# S2_WirelessAudio_CC8530.net
KiCad netlist of a schematic drawn in Altium Designer
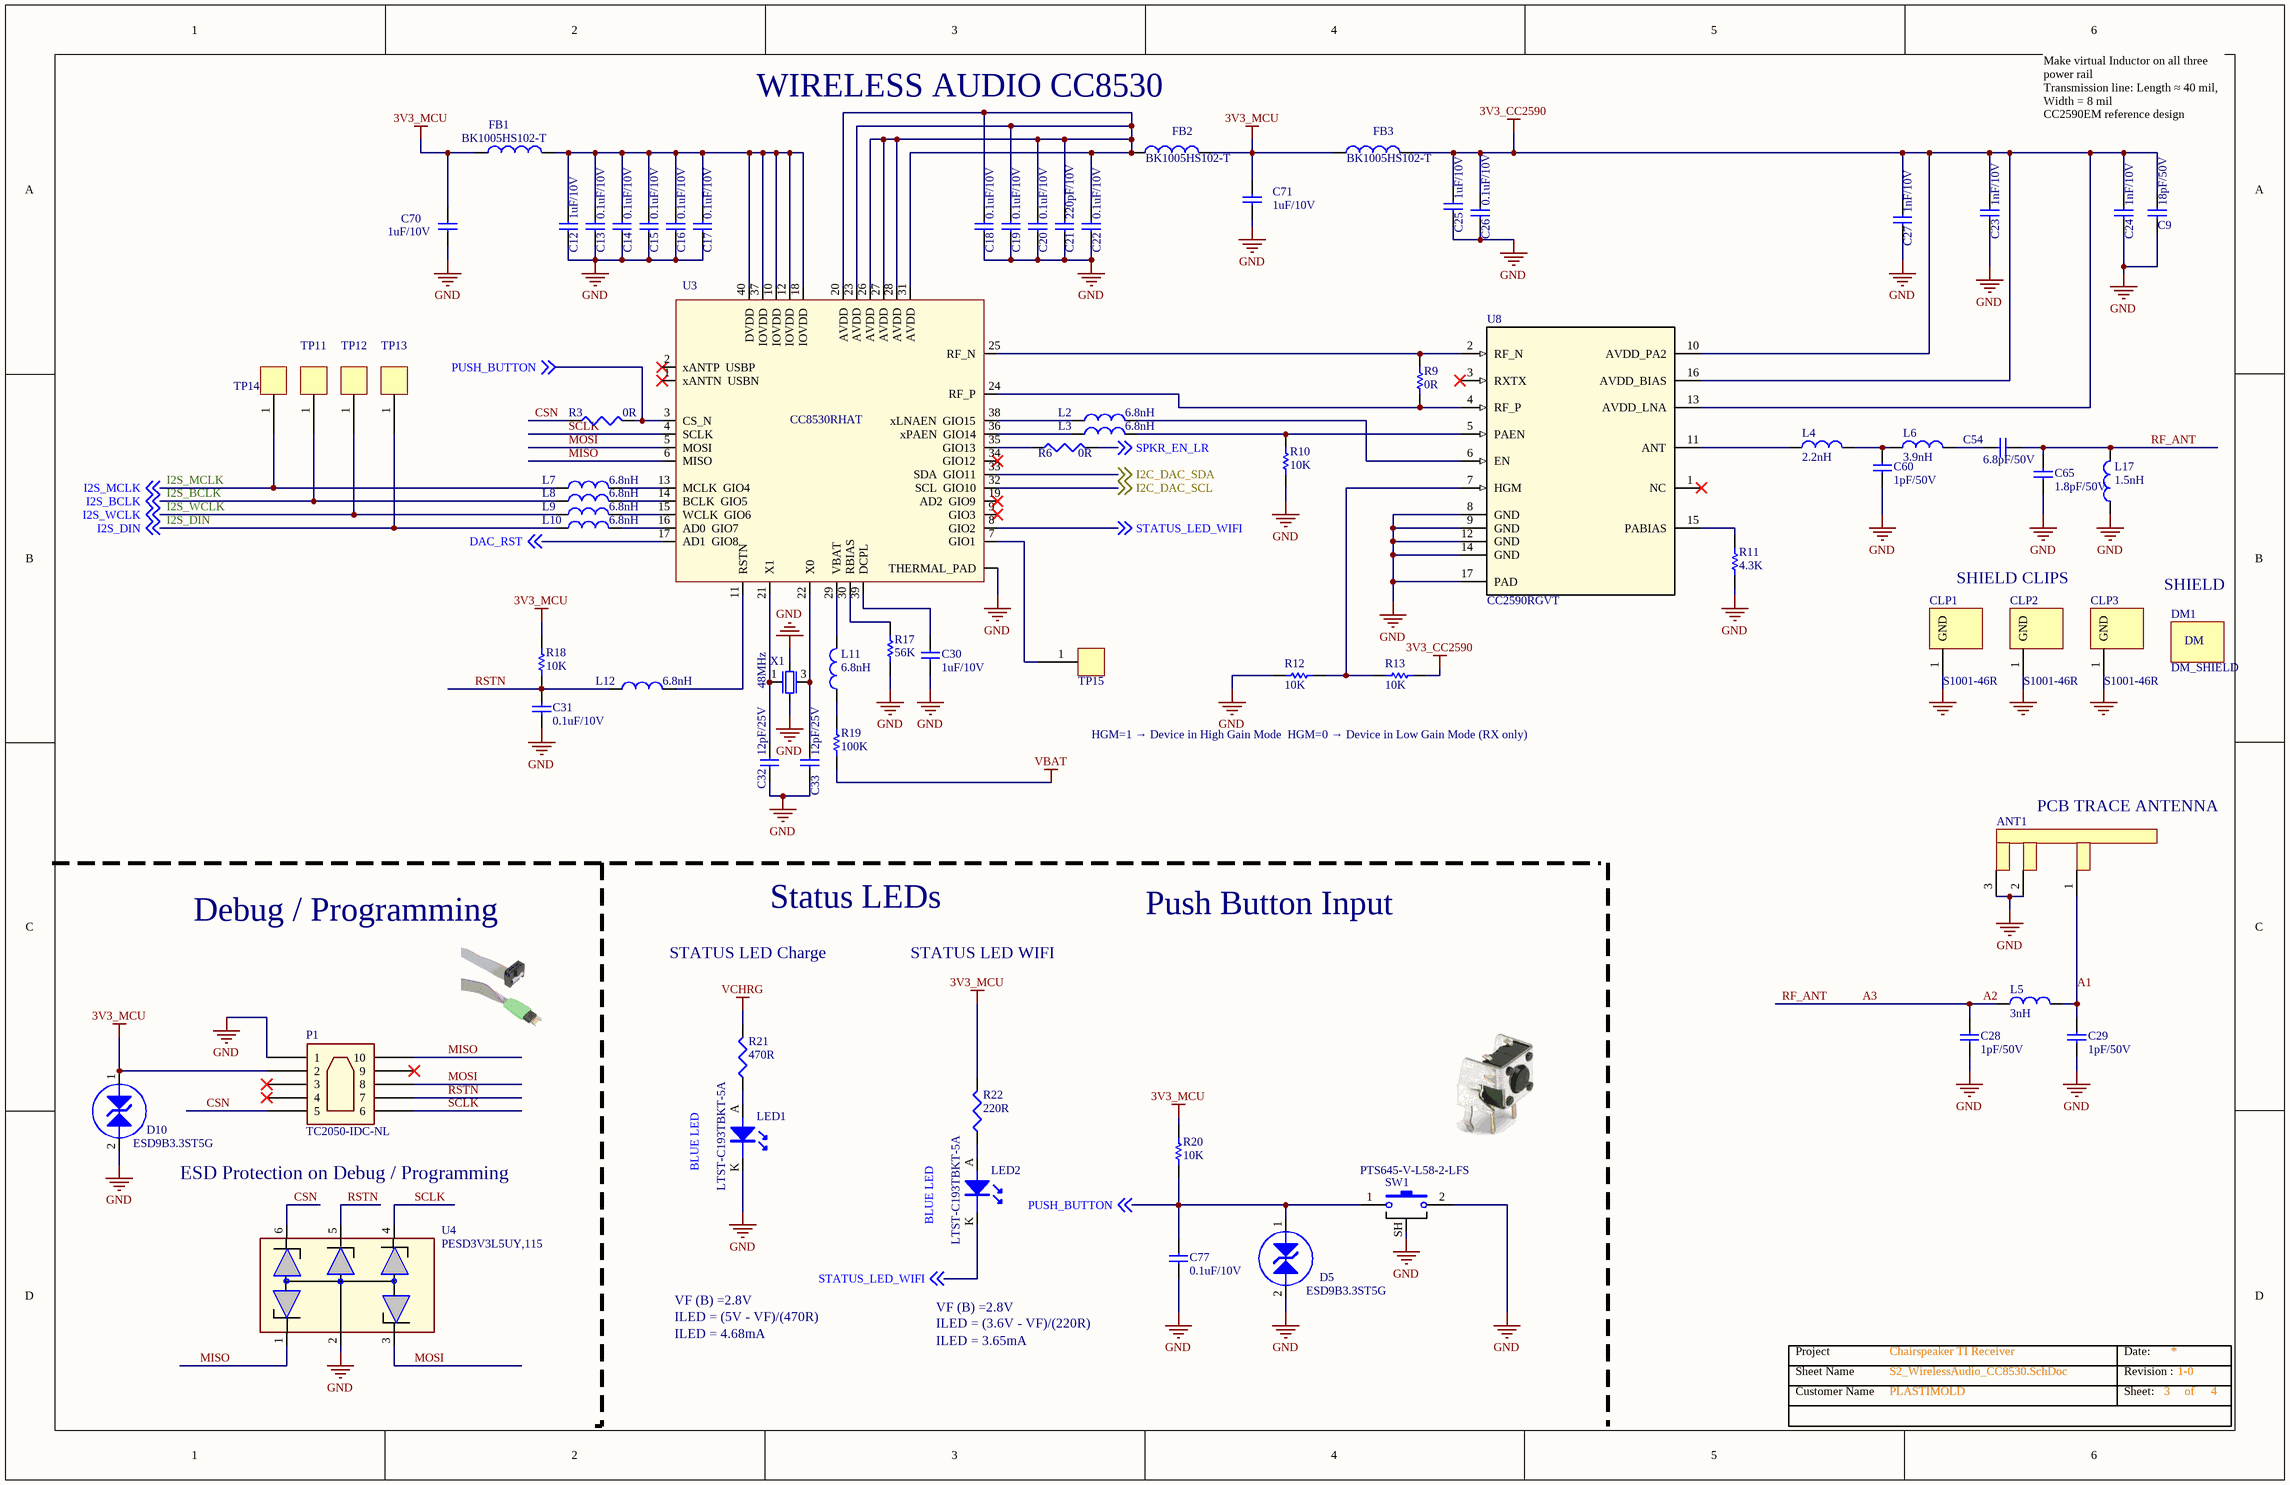
[diagram p0: S2_WirelessAudio_CC8530.SchDoc]

(export (version "E")
  (design (tool "Eeschema 10.0.6"))
  (components
    (comp (ref "ANT1")
      (value "INVERTED F ANTENNA")
      (footprint "ANT")
      (description "=Description1")
      (libsource (lib "TV-Pillow_REV0-1") (part "INVERTED_F"))
    )
    (comp (ref "C9")
      (value "18pF/50V")
      (footprint "CAP_0402_(M1005)")
      (description "=Description1")
      (libsource (lib "Symbol") (part "CAP"))
    )
    (comp (ref "C12")
      (value "1uF/10V")
      (footprint "CAP_0402_(M1005)")
      (description "=Description1")
      (libsource (lib "Nordic Passive DB") (part "CAP"))
    )
    (comp (ref "C13")
      (value "0.1uF/10V")
      (footprint "CAP_0402_(M1005)")
      (description "=Description1")
      (libsource (lib "RC50_REV0-1_INT") (part "CAP_1"))
    )
    (comp (ref "C14")
      (value "0.1uF/10V")
      (footprint "CAP_0402_(M1005)")
      (description "=Description1")
      (libsource (lib "RC50_REV0-1_INT") (part "CAP_1"))
    )
    (comp (ref "C15")
      (value "0.1uF/10V")
      (footprint "CAP_0402_(M1005)")
      (description "=Description1")
      (libsource (lib "RC50_REV0-1_INT") (part "CAP_1"))
    )
    (comp (ref "C16")
      (value "0.1uF/10V")
      (footprint "CAP_0402_(M1005)")
      (description "=Description1")
      (libsource (lib "RC50_REV0-1_INT") (part "CAP_1"))
    )
    (comp (ref "C17")
      (value "0.1uF/10V")
      (footprint "CAP_0402_(M1005)")
      (description "=Description1")
      (libsource (lib "RC50_REV0-1_INT") (part "CAP_1"))
    )
    (comp (ref "C18")
      (value "0.1uF/10V")
      (footprint "CAP_0402_(M1005)")
      (description "=Description1")
      (libsource (lib "RC50_REV0-1_INT") (part "CAP_1"))
    )
    (comp (ref "C19")
      (value "0.1uF/10V")
      (footprint "CAP_0402_(M1005)")
      (description "=Description1")
      (libsource (lib "RC50_REV0-1_INT") (part "CAP_1"))
    )
    (comp (ref "C20")
      (value "0.1uF/10V")
      (footprint "CAP_0402_(M1005)")
      (description "=Description1")
      (libsource (lib "RC50_REV0-1_INT") (part "CAP_1"))
    )
    (comp (ref "C21")
      (value "220pF/10V")
      (footprint "CAP_0402_(M1005)")
      (description "=Description1")
      (libsource (lib "RC50_REV0-1_INT") (part "CAP_1"))
    )
    (comp (ref "C22")
      (value "0.1uF/10V")
      (footprint "CAP_0402_(M1005)")
      (description "=Description1")
      (libsource (lib "RC50_REV0-1_INT") (part "CAP_1"))
    )
    (comp (ref "C23")
      (value "1nF/10V")
      (footprint "CAP_0402_(M1005)")
      (description "=Description1")
      (libsource (lib "RC50_REV0-1_INT") (part "CAP_1"))
    )
    (comp (ref "C24")
      (value "1nF/10V")
      (footprint "CAP_0402_(M1005)")
      (description "=Description1")
      (libsource (lib "RC50_REV0-1_INT") (part "CAP_1"))
    )
    (comp (ref "C25")
      (value "1uF/10V")
      (footprint "CAP_0402_(M1005)")
      (description "=Description1")
      (libsource (lib "Nordic Passive DB") (part "CAP"))
    )
    (comp (ref "C26")
      (value "0.1uF/10V")
      (footprint "CAP_0402_(M1005)")
      (description "=Description1")
      (libsource (lib "RC50_REV0-1_INT") (part "CAP_1"))
    )
    (comp (ref "C27")
      (value "1nF/10V")
      (footprint "CAP_0402_(M1005)")
      (description "=Description1")
      (libsource (lib "RC50_REV0-1_INT") (part "CAP_1"))
    )
    (comp (ref "C28")
      (value "1pF/50V")
      (footprint "CAP_0402_(M1005)")
      (description "=Description1")
      (libsource (lib "Symbol") (part "CAP"))
    )
    (comp (ref "C29")
      (value "1pF/50V")
      (footprint "CAP_0402_(M1005)")
      (description "=Description1")
      (libsource (lib "Symbol") (part "CAP"))
    )
    (comp (ref "C30")
      (value "1uF/10V")
      (footprint "CAP_0402_(M1005)")
      (description "=Description1")
      (libsource (lib "Nordic Passive DB") (part "CAP"))
    )
    (comp (ref "C31")
      (value "0.1uF/10V")
      (footprint "CAP_0402_(M1005)")
      (description "=Description1")
      (libsource (lib "RC50_REV0-1_INT") (part "CAP_1"))
    )
    (comp (ref "C32")
      (value "12pF/25V")
      (footprint "CAP_0402_(M1005)")
      (description "=Description1")
      (libsource (lib "RC50_REV0-1_INT") (part "CAP_1"))
    )
    (comp (ref "C33")
      (value "12pF/25V")
      (footprint "CAP_0402_(M1005)")
      (description "=Description1")
      (libsource (lib "RC50_REV0-1_INT") (part "CAP_1"))
    )
    (comp (ref "C54")
      (value "6.8pF/50V")
      (footprint "CAP_0402_(M1005)")
      (description "=Description1")
      (libsource (lib "Symbol") (part "CAP"))
    )
    (comp (ref "C60")
      (value "1pF/50V")
      (footprint "CAP_0402_(M1005)")
      (description "=Description1")
      (libsource (lib "Symbol") (part "CAP"))
    )
    (comp (ref "C65")
      (value "1.8pF/50V")
      (footprint "CAP_0402_(M1005)")
      (description "=Description1")
      (libsource (lib "Symbol") (part "CAP"))
    )
    (comp (ref "C70")
      (value "1uF/10V")
      (footprint "CAP_0402_(M1005)")
      (description "=Description1")
      (libsource (lib "Nordic Passive DB") (part "CAP"))
    )
    (comp (ref "C71")
      (value "1uF/10V")
      (footprint "CAP_0402_(M1005)")
      (description "=Description1")
      (libsource (lib "Nordic Passive DB") (part "CAP"))
    )
    (comp (ref "C77")
      (value "0.1uF/10V")
      (footprint "CAP_0402_(M1005)")
      (description "=Description1")
      (libsource (lib "RC50_REV0-1_INT") (part "CAP_1"))
    )
    (comp (ref "CLP1")
      (value "S1001-46R")
      (footprint "S1001-46R")
      (description "=Description1")
      (libsource (lib "TV-Pillow_REV0-1") (part "S2711-46R"))
    )
    (comp (ref "CLP2")
      (value "S1001-46R")
      (footprint "S1001-46R")
      (description "=Description1")
      (libsource (lib "TV-Pillow_REV0-1") (part "S2711-46R"))
    )
    (comp (ref "CLP3")
      (value "S1001-46R")
      (footprint "S1001-46R")
      (description "=Description1")
      (libsource (lib "TV-Pillow_REV0-1") (part "S2711-46R"))
    )
    (comp (ref "D5")
      (value "ESD9B3.3ST5G")
      (footprint "SOD-923-BI-DIRECTIONAL")
      (description "TVS DIODE 5V 15.5V 0402")
      (libsource (lib "APC_SCH.") (part "TVS-DIODE"))
    )
    (comp (ref "D10")
      (value "ESD9B3.3ST5G")
      (footprint "SOD-923-BI-DIRECTIONAL")
      (description "TVS DIODE 5V 15.5V 0402")
      (libsource (lib "APC_SCH.") (part "TVS-DIODE"))
    )
    (comp (ref "DM1")
      (value "DM_SHIELD")
      (description "=Description1")
      (libsource (lib "TV-Pillow_REV0-1") (part "DM_SHIELD"))
    )
    (comp (ref "FB1")
      (value "BK1005HS102-T")
      (footprint "IND_0402_(M1005)")
      (description "=Description1")
      (libsource (lib "APC_SCH") (part "FERRITE BEAD"))
    )
    (comp (ref "FB2")
      (value "BK1005HS102-T")
      (footprint "IND_0402_(M1005)")
      (description "=Description1")
      (libsource (lib "APC_SCH") (part "FERRITE BEAD"))
    )
    (comp (ref "FB3")
      (value "BK1005HS102-T")
      (footprint "IND_0402_(M1005)")
      (description "=Description1")
      (libsource (lib "APC_SCH") (part "FERRITE BEAD"))
    )
    (comp (ref "L2")
      (value "6.8nH")
      (footprint "IND_0402_(M1005)")
      (description "=Description1")
      (libsource (lib "Symbol") (part "IND"))
    )
    (comp (ref "L3")
      (value "6.8nH")
      (footprint "IND_0402_(M1005)")
      (description "=Description1")
      (libsource (lib "Symbol") (part "IND"))
    )
    (comp (ref "L4")
      (value "2.2nH")
      (footprint "IND_0402_(M1005)")
      (description "=Description1")
      (libsource (lib "Symbol") (part "IND"))
    )
    (comp (ref "L5")
      (value "3nH")
      (footprint "IND_0402_(M1005)")
      (description "=Description1")
      (libsource (lib "Symbol") (part "IND"))
    )
    (comp (ref "L6")
      (value "3.9nH")
      (footprint "IND_0402_(M1005)")
      (description "=Description1")
      (libsource (lib "Symbol") (part "IND"))
    )
    (comp (ref "L7")
      (value "6.8nH")
      (footprint "IND_0402_(M1005)")
      (description "=Description1")
      (libsource (lib "Symbol") (part "IND"))
    )
    (comp (ref "L8")
      (value "6.8nH")
      (footprint "IND_0402_(M1005)")
      (description "=Description1")
      (libsource (lib "Symbol") (part "IND"))
    )
    (comp (ref "L9")
      (value "6.8nH")
      (footprint "IND_0402_(M1005)")
      (description "=Description1")
      (libsource (lib "Symbol") (part "IND"))
    )
    (comp (ref "L10")
      (value "6.8nH")
      (footprint "IND_0402_(M1005)")
      (description "=Description1")
      (libsource (lib "Symbol") (part "IND"))
    )
    (comp (ref "L11")
      (value "6.8nH")
      (footprint "IND_0402_(M1005)")
      (description "=Description1")
      (libsource (lib "Symbol") (part "IND"))
    )
    (comp (ref "L12")
      (value "6.8nH")
      (footprint "IND_0402_(M1005)")
      (description "=Description1")
      (libsource (lib "Symbol") (part "IND"))
    )
    (comp (ref "L17")
      (value "1.5nH")
      (footprint "IND_0402_(M1005)")
      (description "=Description1")
      (libsource (lib "Symbol") (part "IND"))
    )
    (comp (ref "LED1")
      (value "LTST-C193TBKT-5A")
      (footprint "LED0603_TM")
      (description "LED GREEN 0603 SMD")
      (libsource (lib "APC_SCH") (part "LED"))
    )
    (comp (ref "LED2")
      (value "LTST-C193TBKT-5A")
      (footprint "LED0603_TM")
      (description "LED GREEN 0603 SMD")
      (libsource (lib "APC_SCH") (part "LED"))
    )
    (comp (ref "P1")
      (value "TC2050-IDC-NL")
      (footprint "TC2050-IDC-NL")
      (description "=Description1")
      (libsource (lib "TC2050-IDC-09Mar2012") (part "TC2050-IDC"))
    )
    (comp (ref "R3")
      (value "0R")
      (footprint "RES_0402_(M1005)")
      (description "=Description1")
      (libsource (lib "iTREE3") (part "RES_0R"))
    )
    (comp (ref "R6")
      (value "0R")
      (footprint "RES_0402_(M1005)")
      (description "=Description1")
      (libsource (lib "iTREE3") (part "RES_0R"))
    )
    (comp (ref "R9")
      (value "0R")
      (footprint "RES_0402_(M1005)")
      (description "=Description1")
      (libsource (lib "RC50_REV0-1_INT") (part "RC1206JR-070RL"))
    )
    (comp (ref "R10")
      (value "10K")
      (footprint "RES_0402_(M1005)")
      (description "=Description1")
      (libsource (lib "Symbol") (part "RESISTOR"))
    )
    (comp (ref "R11")
      (value "4.3K")
      (footprint "RES_0402_(M1005)")
      (description "=Description1")
      (libsource (lib "Symbol") (part "RESISTOR"))
    )
    (comp (ref "R12")
      (value "10K")
      (footprint "RES_0402_(M1005)")
      (description "=Description1")
      (libsource (lib "Symbol") (part "RESISTOR"))
    )
    (comp (ref "R13")
      (value "10K")
      (footprint "RES_0402_(M1005)")
      (description "=Description1")
      (libsource (lib "Symbol") (part "RESISTOR"))
    )
    (comp (ref "R17")
      (value "56K")
      (footprint "IND_0402_(M1005)")
      (description "=Description1")
      (libsource (lib "RC50_REV0-1_INT") (part "RC1206JR-070RL"))
    )
    (comp (ref "R18")
      (value "10K")
      (footprint "RES_0402_(M1005)")
      (description "=Description1")
      (libsource (lib "Symbol") (part "RESISTOR"))
    )
    (comp (ref "R19")
      (value "100K")
      (footprint "RES_0402_(M1005)")
      (description "=Description1")
      (libsource (lib "RC50_REV0-1_INT") (part "RC1206JR-070RL"))
    )
    (comp (ref "R20")
      (value "10K")
      (footprint "RES_0402_(M1005)")
      (description "=Description1")
      (libsource (lib "Symbol") (part "RESISTOR"))
    )
    (comp (ref "R21")
      (value "470R")
      (footprint "RES_0402_(M1005)")
      (description "RES 470 OHM 1% 1/16W 0402")
      (libsource (lib "APC_SCH") (part "RES"))
    )
    (comp (ref "R22")
      (value "220R")
      (footprint "RES_0402_(M1005)")
      (description "RES 220 OHM 1% 1/16W 0402")
      (libsource (lib "APC_SCH") (part "RES"))
    )
    (comp (ref "SW1")
      (value "PTS645-V-L58-2-LFS")
      (footprint "SWITCH-PTS645-VL")
      (description "SWITCH TACTILE SPST-NO 0.05A 12V")
      (libsource (lib "Symbol") (part "PB_SWITCH"))
    )
    (comp (ref "TP11")
      (value "TP")
      (footprint "TestP SM 30MIL ROUND")
      (description "=Description1")
      (libsource (lib "RC30 REv01") (part "TP"))
    )
    (comp (ref "TP12")
      (value "TP")
      (footprint "TestP SM 30MIL ROUND")
      (description "=Description1")
      (libsource (lib "RC30 REv01") (part "TP"))
    )
    (comp (ref "TP13")
      (value "TP")
      (footprint "TestP SM 30MIL ROUND")
      (description "=Description1")
      (libsource (lib "RC30 REv01") (part "TP"))
    )
    (comp (ref "TP14")
      (value "TP")
      (footprint "TestP SM 30MIL ROUND")
      (description "=Description1")
      (libsource (lib "RC30 REv01") (part "TP"))
    )
    (comp (ref "TP15")
      (value "TP")
      (footprint "TestP SM 30MIL ROUND")
      (description "=Description1")
      (libsource (lib "") (part "TP_1"))
    )
    (comp (ref "U3")
      (value "CC8530RHAT")
      (footprint "VFQFN40")
      (description "=Description1")
      (libsource (lib "Symbol") (part "CC5820"))
    )
    (comp (ref "U4")
      (value "PESD3V3L5UY,115")
      (footprint "SOT-363")
      (description "=Description1")
      (libsource (lib "TWI_Database_Library") (part "PESD3V3L5UY"))
    )
    (comp (ref "U8")
      (value "CC2590RGVT")
      (footprint "QFN65P400X400X100-17N-D")
      (description "No Description Available")
      (fields
        (field (name "PARTNUMBER") "CC2590RGVR")
        (field (name "MANUFACTURER") "Texas Instruments")
        (field (name "COPYRIGHT") "Copyright (C) 2021 Accelerated Designs. All rights reserved")
      )
      (libsource (lib "Chair_Speaker_TI_Receiver_REV0-4") (part "CC2590RGVT"))
    )
    (comp (ref "X1")
      (value "48MHz")
      (footprint "ECX-2236B")
      (description "=Description1")
      (libsource (lib "Symbol") (part "CRYSTAL_4PIN"))
    )
  )
  (nets
    (net (code "1") (name "/A1") (class "Default")
      (node (ref "ANT1") (pin "1") (pinfunction "1_1") (pintype "passive"))
      (node (ref "C29") (pin "1") (pinfunction "1_1") (pintype "passive"))
      (node (ref "L5") (pin "2") (pinfunction "2_2") (pintype "passive"))
    )
    (net (code "2") (name "/A2") (class "Default")
      (node (ref "C28") (pin "1") (pinfunction "1_1") (pintype "passive"))
      (node (ref "C54") (pin "2") (pinfunction "2_2") (pintype "passive"))
      (node (ref "C65") (pin "2") (pinfunction "2_2") (pintype "passive"))
      (node (ref "L17") (pin "2") (pinfunction "2_2") (pintype "passive"))
      (node (ref "L5") (pin "1") (pinfunction "1_1") (pintype "passive"))
    )
    (net (code "3") (name "/CSN") (class "Default")
      (node (ref "P1") (pin "5") (pinfunction "5_5") (pintype "passive"))
      (node (ref "R3") (pin "1") (pintype "passive"))
      (node (ref "U4") (pin "6") (pinfunction "I/O4_6") (pintype "passive"))
    )
    (net (code "4") (name "/MISO") (class "Default")
      (node (ref "P1") (pin "10") (pinfunction "10_10") (pintype "passive"))
      (node (ref "U3") (pin "6") (pinfunction "MISO_6") (pintype "passive"))
      (node (ref "U4") (pin "1") (pinfunction "I/O1_1") (pintype "passive"))
    )
    (net (code "5") (name "/MOSI") (class "Default")
      (node (ref "P1") (pin "8") (pinfunction "8_8") (pintype "passive"))
      (node (ref "U3") (pin "5") (pinfunction "MOSI_5") (pintype "passive"))
      (node (ref "U4") (pin "3") (pinfunction "I/O2_3") (pintype "passive"))
    )
    (net (code "6") (name "/RSTN") (class "Default")
      (node (ref "C31") (pin "2") (pinfunction "2_2") (pintype "passive"))
      (node (ref "L12") (pin "1") (pinfunction "1_1") (pintype "passive"))
      (node (ref "P1") (pin "7") (pinfunction "7_7") (pintype "passive"))
      (node (ref "R18") (pin "2") (pinfunction "2_2") (pintype "passive"))
      (node (ref "U4") (pin "5") (pinfunction "VDD_5") (pintype "passive"))
    )
    (net (code "7") (name "/SCLK") (class "Default")
      (node (ref "P1") (pin "6") (pinfunction "6_6") (pintype "passive"))
      (node (ref "U3") (pin "4") (pinfunction "SCLK_4") (pintype "passive"))
      (node (ref "U4") (pin "4") (pinfunction "I/O3_4") (pintype "passive"))
    )
    (net (code "8") (name "3V3_CC2590") (class "Default")
      (node (ref "C23") (pin "2") (pinfunction "2_2") (pintype "passive"))
      (node (ref "C24") (pin "2") (pinfunction "2_2") (pintype "passive"))
      (node (ref "C25") (pin "2") (pinfunction "2_2") (pintype "passive"))
      (node (ref "C26") (pin "2") (pinfunction "2_2") (pintype "passive"))
      (node (ref "C27") (pin "2") (pinfunction "2_2") (pintype "passive"))
      (node (ref "C9") (pin "2") (pinfunction "2_2") (pintype "passive"))
      (node (ref "FB3") (pin "2") (pinfunction "2_2") (pintype "passive"))
      (node (ref "R13") (pin "2") (pinfunction "2_2") (pintype "passive"))
      (node (ref "U8") (pin "10") (pinfunction "AVDD_PA2_10") (pintype "power_in"))
      (node (ref "U8") (pin "13") (pinfunction "AVDD_LNA_13") (pintype "power_in"))
      (node (ref "U8") (pin "16") (pinfunction "AVDD_BIAS_16") (pintype "power_in"))
    )
    (net (code "9") (name "3V3_MCU") (class "Default")
      (node (ref "C70") (pin "2") (pinfunction "2_2") (pintype "passive"))
      (node (ref "C71") (pin "2") (pinfunction "2_2") (pintype "passive"))
      (node (ref "D10") (pin "1") (pintype "passive"))
      (node (ref "FB1") (pin "1") (pinfunction "1_1") (pintype "passive"))
      (node (ref "FB2") (pin "2") (pinfunction "2_2") (pintype "passive"))
      (node (ref "FB3") (pin "1") (pinfunction "1_1") (pintype "passive"))
      (node (ref "P1") (pin "2") (pinfunction "2_2") (pintype "passive"))
      (node (ref "R18") (pin "1") (pinfunction "1_1") (pintype "passive"))
      (node (ref "R20") (pin "1") (pinfunction "1_1") (pintype "passive"))
      (node (ref "R22") (pin "2") (pintype "passive"))
    )
    (net (code "10") (name "DAC_RST") (class "Default")
      (node (ref "U3") (pin "17") (pinfunction "AD1__GIO8_17") (pintype "passive"))
    )
    (net (code "11") (name "GND") (class "Default")
      (node (ref "ANT1") (pin "2") (pinfunction "2_2") (pintype "passive"))
      (node (ref "ANT1") (pin "3") (pinfunction "3_3") (pintype "passive"))
      (node (ref "C12") (pin "1") (pinfunction "1_1") (pintype "passive"))
      (node (ref "C13") (pin "1") (pinfunction "1_1") (pintype "passive"))
      (node (ref "C14") (pin "1") (pinfunction "1_1") (pintype "passive"))
      (node (ref "C15") (pin "1") (pinfunction "1_1") (pintype "passive"))
      (node (ref "C16") (pin "1") (pinfunction "1_1") (pintype "passive"))
      (node (ref "C17") (pin "1") (pinfunction "1_1") (pintype "passive"))
      (node (ref "C18") (pin "1") (pinfunction "1_1") (pintype "passive"))
      (node (ref "C19") (pin "1") (pinfunction "1_1") (pintype "passive"))
      (node (ref "C20") (pin "1") (pinfunction "1_1") (pintype "passive"))
      (node (ref "C21") (pin "1") (pinfunction "1_1") (pintype "passive"))
      (node (ref "C22") (pin "1") (pinfunction "1_1") (pintype "passive"))
      (node (ref "C23") (pin "1") (pinfunction "1_1") (pintype "passive"))
      (node (ref "C24") (pin "1") (pinfunction "1_1") (pintype "passive"))
      (node (ref "C25") (pin "1") (pinfunction "1_1") (pintype "passive"))
      (node (ref "C26") (pin "1") (pinfunction "1_1") (pintype "passive"))
      (node (ref "C27") (pin "1") (pinfunction "1_1") (pintype "passive"))
      (node (ref "C28") (pin "2") (pinfunction "2_2") (pintype "passive"))
      (node (ref "C29") (pin "2") (pinfunction "2_2") (pintype "passive"))
      (node (ref "C30") (pin "1") (pinfunction "1_1") (pintype "passive"))
      (node (ref "C31") (pin "1") (pinfunction "1_1") (pintype "passive"))
      (node (ref "C32") (pin "2") (pinfunction "2_2") (pintype "passive"))
      (node (ref "C33") (pin "2") (pinfunction "2_2") (pintype "passive"))
      (node (ref "C60") (pin "2") (pinfunction "2_2") (pintype "passive"))
      (node (ref "C65") (pin "1") (pinfunction "1_1") (pintype "passive"))
      (node (ref "C70") (pin "1") (pinfunction "1_1") (pintype "passive"))
      (node (ref "C71") (pin "1") (pinfunction "1_1") (pintype "passive"))
      (node (ref "C77") (pin "2") (pinfunction "2_2") (pintype "passive"))
      (node (ref "C9") (pin "1") (pinfunction "1_1") (pintype "passive"))
      (node (ref "CLP1") (pin "1") (pinfunction "GND_1") (pintype "passive"))
      (node (ref "CLP2") (pin "1") (pinfunction "GND_1") (pintype "passive"))
      (node (ref "CLP3") (pin "1") (pinfunction "GND_1") (pintype "passive"))
      (node (ref "D10") (pin "2") (pintype "passive"))
      (node (ref "D5") (pin "2") (pintype "passive"))
      (node (ref "L17") (pin "1") (pinfunction "1_1") (pintype "passive"))
      (node (ref "LED1") (pin "K") (pinfunction "K_K") (pintype "passive"))
      (node (ref "P1") (pin "1") (pinfunction "1_1") (pintype "passive"))
      (node (ref "R10") (pin "2") (pinfunction "2_2") (pintype "passive"))
      (node (ref "R11") (pin "1") (pinfunction "1_1") (pintype "passive"))
      (node (ref "R12") (pin "1") (pinfunction "1_1") (pintype "passive"))
      (node (ref "R17") (pin "2") (pinfunction "2_2") (pintype "passive"))
      (node (ref "SW1") (pin "2") (pinfunction "2_2") (pintype "passive"))
      (node (ref "SW1") (pin "SH") (pinfunction "SH_SH") (pintype "passive"))
      (node (ref "U3") (pin "GND") (pinfunction "THERMAL_PAD_GND") (pintype "passive"))
      (node (ref "U4") (pin "2") (pinfunction "GND_2") (pintype "passive"))
      (node (ref "U8") (pin "12") (pinfunction "GND_12") (pintype "power_in"))
      (node (ref "U8") (pin "14") (pinfunction "GND_14") (pintype "power_in"))
      (node (ref "U8") (pin "17") (pinfunction "PAD_17") (pintype "power_in"))
      (node (ref "U8") (pin "8") (pinfunction "GND_8") (pintype "power_in"))
      (node (ref "U8") (pin "9") (pinfunction "GND_9") (pintype "power_in"))
      (node (ref "X1") (pin "2") (pinfunction "2_2") (pintype "passive"))
      (node (ref "X1") (pin "4") (pinfunction "4_4") (pintype "passive"))
    )
    (net (code "12") (name "I2C_DAC_SCL") (class "Default")
      (node (ref "U3") (pin "32") (pinfunction "SCL__GIO10_32") (pintype "passive"))
    )
    (net (code "13") (name "I2C_DAC_SDA") (class "Default")
      (node (ref "U3") (pin "33") (pinfunction "SDA__GIO11_33") (pintype "passive"))
    )
    (net (code "14") (name "I2S_BCLK") (class "Default")
      (node (ref "L8") (pin "1") (pinfunction "1_1") (pintype "passive"))
      (node (ref "TP11") (pin "1") (pintype "passive"))
    )
    (net (code "15") (name "I2S_DIN") (class "Default")
      (node (ref "L10") (pin "1") (pinfunction "1_1") (pintype "passive"))
      (node (ref "TP13") (pin "1") (pintype "passive"))
    )
    (net (code "16") (name "I2S_MCLK") (class "Default")
      (node (ref "L7") (pin "1") (pinfunction "1_1") (pintype "passive"))
      (node (ref "TP14") (pin "1") (pintype "passive"))
    )
    (net (code "17") (name "I2S_WCLK") (class "Default")
      (node (ref "L9") (pin "1") (pinfunction "1_1") (pintype "passive"))
      (node (ref "TP12") (pin "1") (pintype "passive"))
    )
    (net (code "18") (name "Net-(C18-Pad2)") (class "Default")
      (node (ref "C18") (pin "2") (pinfunction "2_2") (pintype "passive"))
      (node (ref "C19") (pin "2") (pinfunction "2_2") (pintype "passive"))
      (node (ref "C20") (pin "2") (pinfunction "2_2") (pintype "passive"))
      (node (ref "C21") (pin "2") (pinfunction "2_2") (pintype "passive"))
      (node (ref "C22") (pin "2") (pinfunction "2_2") (pintype "passive"))
      (node (ref "FB2") (pin "1") (pinfunction "1_1") (pintype "passive"))
      (node (ref "U3") (pin "20") (pinfunction "AVDD_20") (pintype "passive"))
      (node (ref "U3") (pin "23") (pinfunction "AVDD_23") (pintype "passive"))
      (node (ref "U3") (pin "26") (pinfunction "AVDD_26") (pintype "passive"))
      (node (ref "U3") (pin "27") (pinfunction "AVDD_27") (pintype "passive"))
      (node (ref "U3") (pin "28") (pinfunction "AVDD_28") (pintype "passive"))
      (node (ref "U3") (pin "31") (pinfunction "AVDD_31") (pintype "passive"))
    )
    (net (code "19") (name "Net-(C54-Pad1)") (class "Default")
      (node (ref "C54") (pin "1") (pinfunction "1_1") (pintype "passive"))
      (node (ref "L6") (pin "2") (pinfunction "2_2") (pintype "passive"))
    )
    (net (code "20") (name "Net-(C60-Pad1)") (class "Default")
      (node (ref "C60") (pin "1") (pinfunction "1_1") (pintype "passive"))
      (node (ref "L4") (pin "2") (pinfunction "2_2") (pintype "passive"))
      (node (ref "L6") (pin "1") (pinfunction "1_1") (pintype "passive"))
    )
    (net (code "21") (name "Net-(L11-Pad1)") (class "Default")
      (node (ref "L11") (pin "1") (pinfunction "1_1") (pintype "passive"))
      (node (ref "R19") (pin "1") (pinfunction "1_1") (pintype "passive"))
    )
    (net (code "22") (name "Net-(LED1-PadA)") (class "Default")
      (node (ref "LED1") (pin "A") (pinfunction "A_A") (pintype "passive"))
      (node (ref "R21") (pin "1") (pintype "passive"))
    )
    (net (code "23") (name "Net-(LED2-PadA)") (class "Default")
      (node (ref "LED2") (pin "A") (pinfunction "A_A") (pintype "passive"))
      (node (ref "R22") (pin "1") (pintype "passive"))
    )
    (net (code "24") (name "Net-(U3-AD0__GIO7)") (class "Default")
      (node (ref "L10") (pin "2") (pinfunction "2_2") (pintype "passive"))
      (node (ref "U3") (pin "16") (pinfunction "AD0__GIO7_16") (pintype "passive"))
    )
    (net (code "25") (name "Net-(U3-BCLK__GIO5)") (class "Default")
      (node (ref "L8") (pin "2") (pinfunction "2_2") (pintype "passive"))
      (node (ref "U3") (pin "14") (pinfunction "BCLK__GIO5_14") (pintype "passive"))
    )
    (net (code "26") (name "Net-(U3-DCPL)") (class "Default")
      (node (ref "C30") (pin "2") (pinfunction "2_2") (pintype "passive"))
      (node (ref "U3") (pin "39") (pinfunction "DCPL_39") (pintype "passive"))
    )
    (net (code "27") (name "Net-(U3-DVDD)") (class "Default")
      (node (ref "C12") (pin "2") (pinfunction "2_2") (pintype "passive"))
      (node (ref "C13") (pin "2") (pinfunction "2_2") (pintype "passive"))
      (node (ref "C14") (pin "2") (pinfunction "2_2") (pintype "passive"))
      (node (ref "C15") (pin "2") (pinfunction "2_2") (pintype "passive"))
      (node (ref "C16") (pin "2") (pinfunction "2_2") (pintype "passive"))
      (node (ref "C17") (pin "2") (pinfunction "2_2") (pintype "passive"))
      (node (ref "FB1") (pin "2") (pinfunction "2_2") (pintype "passive"))
      (node (ref "U3") (pin "10") (pinfunction "IOVDD_10") (pintype "passive"))
      (node (ref "U3") (pin "12") (pinfunction "IOVDD_12") (pintype "passive"))
      (node (ref "U3") (pin "18") (pinfunction "IOVDD_18") (pintype "passive"))
      (node (ref "U3") (pin "37") (pinfunction "IOVDD_37") (pintype "passive"))
      (node (ref "U3") (pin "40") (pinfunction "DVDD_40") (pintype "passive"))
    )
    (net (code "28") (name "Net-(U3-GIO1)") (class "Default")
      (node (ref "TP15") (pin "1") (pintype "passive"))
      (node (ref "U3") (pin "7") (pinfunction "GIO1_7") (pintype "passive"))
    )
    (net (code "29") (name "Net-(U3-GIO13)") (class "Default")
      (node (ref "R6") (pin "1") (pintype "passive"))
      (node (ref "U3") (pin "35") (pinfunction "GIO13_35") (pintype "passive"))
    )
    (net (code "30") (name "Net-(U3-MCLK__GIO4)") (class "Default")
      (node (ref "L7") (pin "2") (pinfunction "2_2") (pintype "passive"))
      (node (ref "U3") (pin "13") (pinfunction "MCLK__GIO4_13") (pintype "passive"))
    )
    (net (code "31") (name "Net-(U3-RBIAS)") (class "Default")
      (node (ref "R17") (pin "1") (pinfunction "1_1") (pintype "passive"))
      (node (ref "U3") (pin "30") (pinfunction "RBIAS_30") (pintype "passive"))
    )
    (net (code "32") (name "Net-(U3-RF_N)") (class "Default")
      (node (ref "R9") (pin "2") (pinfunction "2_2") (pintype "passive"))
      (node (ref "U3") (pin "25") (pinfunction "RF_N_25") (pintype "passive"))
      (node (ref "U8") (pin "2") (pinfunction "RF_N_2") (pintype "input"))
    )
    (net (code "33") (name "Net-(U3-RF_P)") (class "Default")
      (node (ref "R9") (pin "1") (pinfunction "1_1") (pintype "passive"))
      (node (ref "U3") (pin "24") (pinfunction "RF_P_24") (pintype "passive"))
      (node (ref "U8") (pin "4") (pinfunction "RF_P_4") (pintype "input"))
    )
    (net (code "34") (name "Net-(U3-RSTN)") (class "Default")
      (node (ref "L12") (pin "2") (pinfunction "2_2") (pintype "passive"))
      (node (ref "U3") (pin "11") (pinfunction "RSTN_11") (pintype "passive"))
    )
    (net (code "35") (name "Net-(U3-VBAT)") (class "Default")
      (node (ref "L11") (pin "2") (pinfunction "2_2") (pintype "passive"))
      (node (ref "U3") (pin "29") (pinfunction "VBAT_29") (pintype "passive"))
    )
    (net (code "36") (name "Net-(U3-WCLK__GIO6)") (class "Default")
      (node (ref "L9") (pin "2") (pinfunction "2_2") (pintype "passive"))
      (node (ref "U3") (pin "15") (pinfunction "WCLK__GIO6_15") (pintype "passive"))
    )
    (net (code "37") (name "Net-(U3-X0)") (class "Default")
      (node (ref "C33") (pin "1") (pinfunction "1_1") (pintype "passive"))
      (node (ref "U3") (pin "22") (pinfunction "X0_22") (pintype "passive"))
      (node (ref "X1") (pin "3") (pinfunction "3_3") (pintype "passive"))
    )
    (net (code "38") (name "Net-(U3-X1)") (class "Default")
      (node (ref "C32") (pin "1") (pinfunction "1_1") (pintype "passive"))
      (node (ref "U3") (pin "21") (pinfunction "X1_21") (pintype "passive"))
      (node (ref "X1") (pin "1") (pinfunction "1_1") (pintype "passive"))
    )
    (net (code "39") (name "Net-(U3-xLNAEN__GIO15)") (class "Default")
      (node (ref "L2") (pin "1") (pinfunction "1_1") (pintype "passive"))
      (node (ref "U3") (pin "38") (pinfunction "xLNAEN__GIO15_38") (pintype "passive"))
    )
    (net (code "40") (name "Net-(U3-xPAEN__GIO14)") (class "Default")
      (node (ref "L3") (pin "1") (pinfunction "1_1") (pintype "passive"))
      (node (ref "U3") (pin "36") (pinfunction "xPAEN__GIO14_36") (pintype "passive"))
    )
    (net (code "41") (name "Net-(U8-ANT)") (class "Default")
      (node (ref "L4") (pin "1") (pinfunction "1_1") (pintype "passive"))
      (node (ref "U8") (pin "11") (pinfunction "ANT_11") (pintype "passive"))
    )
    (net (code "42") (name "Net-(U8-EN)") (class "Default")
      (node (ref "L2") (pin "2") (pinfunction "2_2") (pintype "passive"))
      (node (ref "U8") (pin "6") (pinfunction "EN_6") (pintype "input"))
    )
    (net (code "43") (name "Net-(U8-HGM)") (class "Default")
      (node (ref "R12") (pin "2") (pinfunction "2_2") (pintype "passive"))
      (node (ref "R13") (pin "1") (pinfunction "1_1") (pintype "passive"))
      (node (ref "U8") (pin "7") (pinfunction "HGM_7") (pintype "input"))
    )
    (net (code "44") (name "Net-(U8-PABIAS)") (class "Default")
      (node (ref "R11") (pin "2") (pinfunction "2_2") (pintype "passive"))
      (node (ref "U8") (pin "15") (pinfunction "PABIAS_15") (pintype "passive"))
    )
    (net (code "45") (name "Net-(U8-PAEN)") (class "Default")
      (node (ref "L3") (pin "2") (pinfunction "2_2") (pintype "passive"))
      (node (ref "R10") (pin "1") (pinfunction "1_1") (pintype "passive"))
      (node (ref "U8") (pin "5") (pinfunction "PAEN_5") (pintype "input"))
    )
    (net (code "46") (name "PUSH_BUTTON") (class "Default")
      (node (ref "C77") (pin "1") (pinfunction "1_1") (pintype "passive"))
      (node (ref "D5") (pin "1") (pintype "passive"))
      (node (ref "R20") (pin "2") (pinfunction "2_2") (pintype "passive"))
      (node (ref "R3") (pin "2") (pintype "passive"))
      (node (ref "SW1") (pin "1") (pinfunction "1_1") (pintype "passive"))
      (node (ref "U3") (pin "3") (pinfunction "CS_N_3") (pintype "passive"))
    )
    (net (code "47") (name "SPKR_EN_LR") (class "Default") (node (ref "R6") (pin "2") (pintype "passive")))
    (net (code "48") (name "STATUS_LED_WIFI") (class "Default")
      (node (ref "LED2") (pin "K") (pinfunction "K_K") (pintype "passive"))
      (node (ref "U3") (pin "8") (pinfunction "GIO2_8") (pintype "passive"))
    )
    (net (code "49") (name "VBAT") (class "Default")
      (node (ref "R19") (pin "2") (pinfunction "2_2") (pintype "passive"))
    )
    (net (code "50") (name "VCHRG") (class "Default") (node (ref "R21") (pin "2") (pintype "passive")))
    (net (code "51") (name "unconnected-(P1-Pad3)") (class "Default")
      (node (ref "P1") (pin "3") (pinfunction "3_3") (pintype "passive+no_connect"))
    )
    (net (code "52") (name "unconnected-(P1-Pad4)") (class "Default")
      (node (ref "P1") (pin "4") (pinfunction "4_4") (pintype "passive+no_connect"))
    )
    (net (code "53") (name "unconnected-(P1-Pad9)") (class "Default")
      (node (ref "P1") (pin "9") (pinfunction "9_9") (pintype "passive+no_connect"))
    )
    (net (code "54") (name "unconnected-(U3-AD2__GIO9-Pad19)") (class "Default")
      (node (ref "U3") (pin "19") (pinfunction "AD2__GIO9_19") (pintype "passive+no_connect"))
    )
    (net (code "55") (name "unconnected-(U3-GIO3-Pad9)") (class "Default")
      (node (ref "U3") (pin "9") (pinfunction "GIO3_9") (pintype "passive+no_connect"))
    )
    (net (code "56") (name "unconnected-(U3-GIO12-Pad34)") (class "Default")
      (node (ref "U3") (pin "34") (pinfunction "GIO12_34") (pintype "passive+no_connect"))
    )
    (net (code "57") (name "unconnected-(U3-xANTN__USBN-Pad1)") (class "Default")
      (node (ref "U3") (pin "1") (pinfunction "xANTN__USBN_1") (pintype "passive+no_connect"))
    )
    (net (code "58") (name "unconnected-(U3-xANTP__USBP-Pad2)") (class "Default")
      (node (ref "U3") (pin "2") (pinfunction "xANTP__USBP_2") (pintype "passive+no_connect"))
    )
    (net (code "59") (name "unconnected-(U8-NC-Pad1)") (class "Default")
      (node (ref "U8") (pin "1") (pinfunction "NC_1") (pintype "passive+no_connect"))
    )
    (net (code "60") (name "unconnected-(U8-RXTX-Pad3)") (class "Default")
      (node (ref "U8") (pin "3") (pinfunction "RXTX_3") (pintype "input+no_connect"))
    )
  )
)
